# diode_winductor.net
KiCad netlist of a schematic drawn in EAGLE
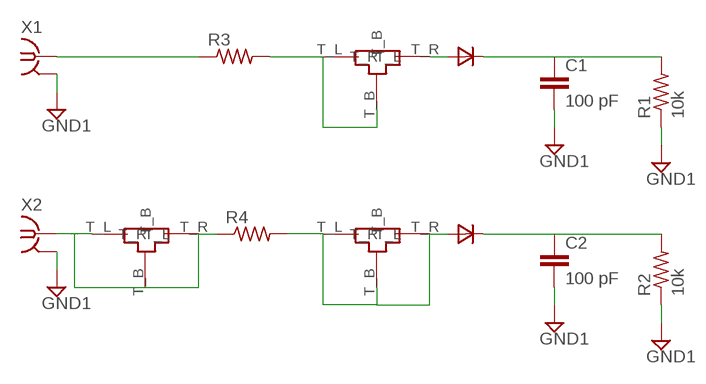
[diagram p0: schematic, sheet 1]

(export (version "E")
  (design (tool "Eeschema 10.0.6"))
  (components
    (comp (ref "C1")
      (value "100 pF")
      (footprint "eagle-import:C0603")
      (libsource (lib "eagle-import") (part "C-EUC0603"))
    )
    (comp (ref "C2")
      (value "100 pF")
      (footprint "eagle-import:C0603")
      (libsource (lib "eagle-import") (part "C-EUC0603"))
    )
    (comp (ref "INPUT")
      (value "TEE_TL1")
      (footprint "eagle-import:TEE_TL1")
      (libsource (lib "eagle-import") (part "TEE_TL1"))
    )
    (comp (ref "INPUT1")
      (value "TEE_TL1")
      (footprint "eagle-import:TEE_TL1")
      (libsource (lib "eagle-import") (part "TEE_TL1"))
    )
    (comp (ref "INPUT2")
      (value "TEE_TL1")
      (footprint "eagle-import:TEE_TL1")
      (libsource (lib "eagle-import") (part "TEE_TL1"))
    )
    (comp (ref "R1")
      (value "10k")
      (footprint "eagle-import:M1206")
      (libsource (lib "eagle-import") (part "R-US_M1206"))
    )
    (comp (ref "R2")
      (value "10k")
      (footprint "eagle-import:M1206")
      (libsource (lib "eagle-import") (part "R-US_M1206"))
    )
    (comp (ref "R3")
      (value "R-US_R0603")
      (footprint "eagle-import:R0603")
      (libsource (lib "eagle-import") (part "R-US_R0603"))
    )
    (comp (ref "R4")
      (value "R-US_R0603")
      (footprint "eagle-import:R0603")
      (libsource (lib "eagle-import") (part "R-US_R0603"))
    )
    (comp (ref "U$1")
      (value "HSMS-2850")
      (footprint "eagle-import:HSMS-2850")
      (libsource (lib "eagle-import") (part "HSMS-2850"))
    )
    (comp (ref "U$2")
      (value "HSMS-2850")
      (footprint "eagle-import:HSMS-2850")
      (libsource (lib "eagle-import") (part "HSMS-2850"))
    )
    (comp (ref "X1")
      (value "SMA-142-0701-801/806")
      (footprint "eagle-import:J502-ND-142-0701-801_806")
      (fields (field (name "MF") "JOHNSON COMPONENTS") (field (name "MPN") "142-0701-801"))
      (libsource (lib "eagle-import") (part "SMA-142-0701-801/806"))
    )
    (comp (ref "X2")
      (value "SMA-142-0701-801/806")
      (footprint "eagle-import:J502-ND-142-0701-801_806")
      (fields (field (name "MF") "JOHNSON COMPONENTS") (field (name "MPN") "142-0701-801"))
      (libsource (lib "eagle-import") (part "SMA-142-0701-801/806"))
    )
  )
  (nets
    (net (code "1") (name "/INPUT") (class "Default")
      (node (ref "INPUT") (pin "T_B") (pinfunction "T_B_T_B") (pintype "bidirectional"))
      (node (ref "INPUT") (pin "T_L") (pinfunction "T_L_T_L") (pintype "bidirectional"))
      (node (ref "INPUT") (pin "T_R") (pinfunction "T_R_T_R") (pintype "bidirectional"))
      (node (ref "R3") (pin "2") (pinfunction "2_2") (pintype "passive"))
      (node (ref "U$1") (pin "A") (pinfunction "A_A") (pintype "passive"))
    )
    (net (code "2") (name "GND1") (class "Default")
      (node (ref "C1") (pin "2") (pinfunction "2_2") (pintype "passive"))
      (node (ref "C2") (pin "2") (pinfunction "2_2") (pintype "passive"))
      (node (ref "R1") (pin "1") (pinfunction "1_1") (pintype "passive"))
      (node (ref "R2") (pin "1") (pinfunction "1_1") (pintype "passive"))
      (node (ref "X1") (pin "G@1") (pinfunction "2_G@1") (pintype "passive"))
      (node (ref "X1") (pin "G@2") (pinfunction "2_G@2") (pintype "passive"))
      (node (ref "X1") (pin "G@3") (pinfunction "2_G@3") (pintype "passive"))
      (node (ref "X1") (pin "G@4") (pinfunction "2_G@4") (pintype "passive"))
      (node (ref "X2") (pin "G@1") (pinfunction "2_G@1") (pintype "passive"))
      (node (ref "X2") (pin "G@2") (pinfunction "2_G@2") (pintype "passive"))
      (node (ref "X2") (pin "G@3") (pinfunction "2_G@3") (pintype "passive"))
      (node (ref "X2") (pin "G@4") (pinfunction "2_G@4") (pintype "passive"))
    )
    (net (code "3") (name "Net-(C1-Pad1)") (class "Default")
      (node (ref "C1") (pin "1") (pinfunction "1_1") (pintype "passive"))
      (node (ref "R1") (pin "2") (pinfunction "2_2") (pintype "passive"))
      (node (ref "U$1") (pin "C") (pinfunction "C_C") (pintype "passive"))
    )
    (net (code "4") (name "Net-(C2-Pad1)") (class "Default")
      (node (ref "C2") (pin "1") (pinfunction "1_1") (pintype "passive"))
      (node (ref "R2") (pin "2") (pinfunction "2_2") (pintype "passive"))
      (node (ref "U$2") (pin "C") (pinfunction "C_C") (pintype "passive"))
    )
    (net (code "5") (name "Net-(INPUT1-PadT_B)") (class "Default")
      (node (ref "INPUT1") (pin "T_B") (pinfunction "T_B_T_B") (pintype "bidirectional"))
      (node (ref "INPUT1") (pin "T_L") (pinfunction "T_L_T_L") (pintype "bidirectional"))
      (node (ref "INPUT1") (pin "T_R") (pinfunction "T_R_T_R") (pintype "bidirectional"))
      (node (ref "R4") (pin "2") (pinfunction "2_2") (pintype "passive"))
      (node (ref "U$2") (pin "A") (pinfunction "A_A") (pintype "passive"))
    )
    (net (code "6") (name "Net-(INPUT2-PadT_B)") (class "Default")
      (node (ref "INPUT2") (pin "T_B") (pinfunction "T_B_T_B") (pintype "bidirectional"))
      (node (ref "INPUT2") (pin "T_L") (pinfunction "T_L_T_L") (pintype "bidirectional"))
      (node (ref "INPUT2") (pin "T_R") (pinfunction "T_R_T_R") (pintype "bidirectional"))
      (node (ref "R4") (pin "1") (pinfunction "1_1") (pintype "passive"))
      (node (ref "X2") (pin "1") (pinfunction "1_1") (pintype "passive"))
    )
    (net (code "7") (name "Net-(R3-Pad1)") (class "Default")
      (node (ref "R3") (pin "1") (pinfunction "1_1") (pintype "passive"))
      (node (ref "X1") (pin "1") (pinfunction "1_1") (pintype "passive"))
    )
  )
)
